# sch.net
KiCad netlist of a schematic drawn in Altium Designer
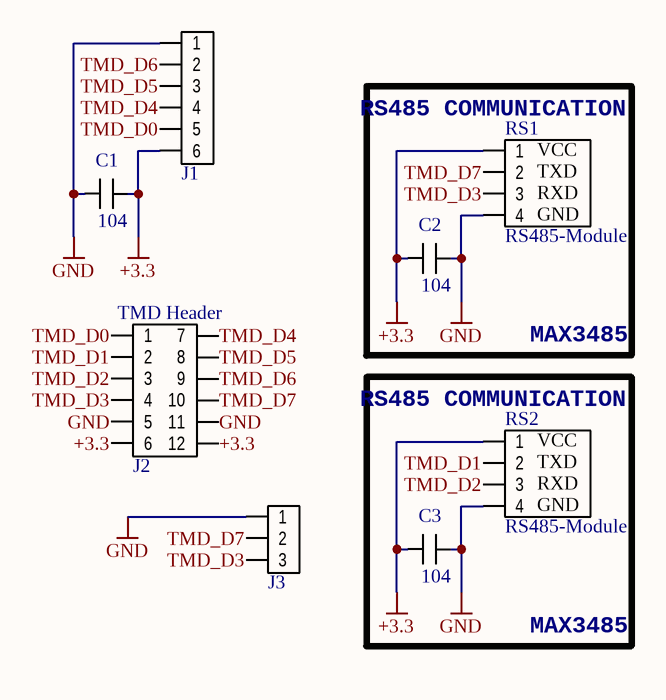
[diagram p0: sch.SchDoc]

(export (version "E")
  (design (tool "Eeschema 10.0.6"))
  (components
    (comp (ref "C1")
      (value "104")
      (footprint "CAP-CERAMIC-100mil-BPAD")
      (description "Capacitor")
      (libsource (lib "Sch") (part "CAP"))
    )
    (comp (ref "C2")
      (value "104")
      (footprint "CAP-CERAMIC-100mil-BPAD")
      (description "Capacitor")
      (libsource (lib "Sch") (part "CAP"))
    )
    (comp (ref "C3")
      (value "104")
      (footprint "CAP-CERAMIC-100mil-BPAD")
      (description "Capacitor")
      (libsource (lib "Sch") (part "CAP"))
    )
    (comp (ref "J1")
      (value "Header 6x1")
      (footprint "TER-J6x1-M-2.54mm-BPAD")
      (libsource (lib "Sch") (part "Header 6x1"))
    )
    (comp (ref "J2")
      (value "TMD Header")
      (footprint "TER-J6x2-M-2.54mm-V-BPAD")
      (libsource (lib "Sch") (part "Header 6x2"))
    )
    (comp (ref "J3")
      (value "Header 3x1")
      (footprint "TER-J3x1-M-2.54mm-BPAD")
      (libsource (lib "Sch") (part "Header 3x1"))
    )
    (comp (ref "RS1")
      (value "RS485-Module")
      (footprint "COMM-RS485-to-TTL-MODULE-SIMPLIFIED-BPAD")
      (description "https://www.thegioiic.com/products/mach-chuyen-doi-rs485-to-ttl")
      (libsource (lib "Sch") (part "COMM RS485-to-TTL-simplified"))
    )
    (comp (ref "RS2")
      (value "RS485-Module")
      (footprint "COMM-RS485-to-TTL-MODULE-SIMPLIFIED-BPAD")
      (description "https://www.thegioiic.com/products/mach-chuyen-doi-rs485-to-ttl")
      (libsource (lib "Sch") (part "COMM RS485-to-TTL-simplified"))
    )
  )
  (nets
    (net (code "1") (name "+3.3") (class "Default")
      (node (ref "C1") (pin "2") (pinfunction "2_2") (pintype "passive"))
      (node (ref "C2") (pin "1") (pinfunction "1_1") (pintype "passive"))
      (node (ref "C3") (pin "1") (pinfunction "1_1") (pintype "passive"))
      (node (ref "J1") (pin "6") (pinfunction "6_6") (pintype "passive"))
      (node (ref "J2") (pin "12") (pinfunction "12_12") (pintype "passive"))
      (node (ref "J2") (pin "6") (pinfunction "6_6") (pintype "passive"))
      (node (ref "RS1") (pin "1") (pinfunction "1_1") (pintype "passive"))
      (node (ref "RS2") (pin "1") (pinfunction "1_1") (pintype "passive"))
    )
    (net (code "2") (name "/TMD_D0") (class "Default")
      (node (ref "J1") (pin "5") (pinfunction "5_5") (pintype "passive"))
      (node (ref "J2") (pin "1") (pinfunction "1_1") (pintype "passive"))
    )
    (net (code "3") (name "/TMD_D1") (class "Default")
      (node (ref "J2") (pin "2") (pinfunction "2_2") (pintype "passive"))
      (node (ref "RS2") (pin "2") (pinfunction "2_2") (pintype "passive"))
    )
    (net (code "4") (name "/TMD_D2") (class "Default")
      (node (ref "J2") (pin "3") (pinfunction "3_3") (pintype "passive"))
      (node (ref "RS2") (pin "3") (pinfunction "3_3") (pintype "passive"))
    )
    (net (code "5") (name "/TMD_D3") (class "Default")
      (node (ref "J2") (pin "4") (pinfunction "4_4") (pintype "passive"))
      (node (ref "J3") (pin "3") (pinfunction "3_3") (pintype "passive"))
      (node (ref "RS1") (pin "3") (pinfunction "3_3") (pintype "passive"))
    )
    (net (code "6") (name "/TMD_D4") (class "Default")
      (node (ref "J1") (pin "4") (pinfunction "4_4") (pintype "passive"))
      (node (ref "J2") (pin "7") (pinfunction "7_7") (pintype "passive"))
    )
    (net (code "7") (name "/TMD_D5") (class "Default")
      (node (ref "J1") (pin "3") (pinfunction "3_3") (pintype "passive"))
      (node (ref "J2") (pin "8") (pinfunction "8_8") (pintype "passive"))
    )
    (net (code "8") (name "/TMD_D6") (class "Default")
      (node (ref "J1") (pin "2") (pinfunction "2_2") (pintype "passive"))
      (node (ref "J2") (pin "9") (pinfunction "9_9") (pintype "passive"))
    )
    (net (code "9") (name "/TMD_D7") (class "Default")
      (node (ref "J2") (pin "10") (pinfunction "10_10") (pintype "passive"))
      (node (ref "J3") (pin "2") (pinfunction "2_2") (pintype "passive"))
      (node (ref "RS1") (pin "2") (pinfunction "2_2") (pintype "passive"))
    )
    (net (code "10") (name "GND") (class "Default")
      (node (ref "C1") (pin "1") (pinfunction "1_1") (pintype "passive"))
      (node (ref "C2") (pin "2") (pinfunction "2_2") (pintype "passive"))
      (node (ref "C3") (pin "2") (pinfunction "2_2") (pintype "passive"))
      (node (ref "J1") (pin "1") (pinfunction "1_1") (pintype "passive"))
      (node (ref "J2") (pin "11") (pinfunction "11_11") (pintype "passive"))
      (node (ref "J2") (pin "5") (pinfunction "5_5") (pintype "passive"))
      (node (ref "J3") (pin "1") (pinfunction "1_1") (pintype "passive"))
      (node (ref "RS1") (pin "4") (pinfunction "4_4") (pintype "passive"))
      (node (ref "RS2") (pin "4") (pinfunction "4_4") (pintype "passive"))
    )
  )
)
